# Main.net
KiCad netlist of a schematic drawn in Altium Designer
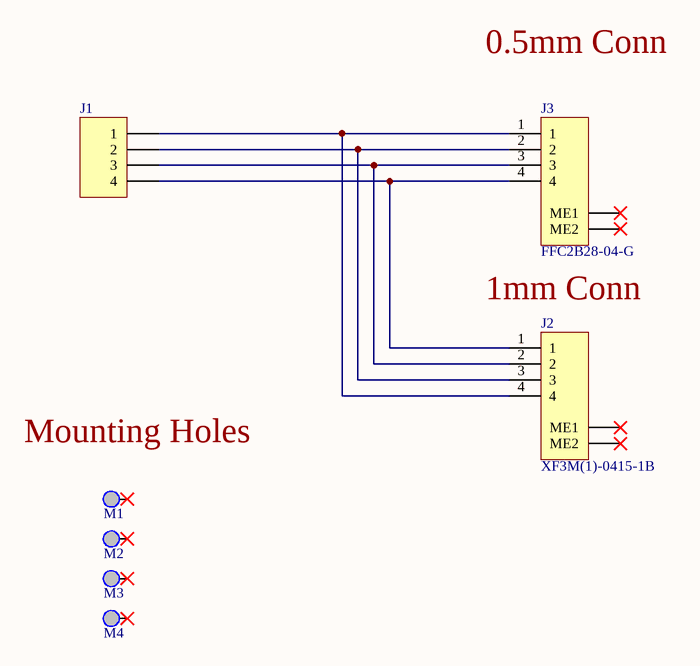
[diagram p0: Main.SchDoc]

(export (version "E")
  (design (tool "Eeschema 10.0.6"))
  (components
    (comp (ref "J1")
      (value "61300411121")
      (footprint "HDR-V-1X4")
      (description "Header, 4-Pin, 0.1\"")
      (libsource (lib "intercreate") (part "HDR-V-1X4-M"))
    )
    (comp (ref "J2")
      (value "XF3M(1)-0415-1B")
      (footprint "CONN-FFC-H-4P-1MM")
      (description "FFC & FPC Connectors RotaryBackLock 1.0mm Dual Contact 4pin")
      (libsource (lib "intercreate") (part "CONN-FFC-H-4P-1MM"))
    )
    (comp (ref "J3")
      (value "FFC2B28-04-G")
      (footprint "CONN-FFC-H-4P-0.5MM")
      (description "4W, 0.5MM Ffc Con, R/a, Dual Cont")
      (libsource (lib "intercreate") (part "CONN-FFC-H-4P-0.5MM"))
    )
    (comp (ref "M1")
      (value "MTG_HOLE")
      (footprint "MH_P_2.5MM")
      (description "MTG HOLE PLATED VARIOUS SIZES")
      (libsource (lib "intercreate") (part "MTG_HOLE"))
    )
    (comp (ref "M2")
      (value "MTG_HOLE")
      (footprint "MH_P_2.5MM")
      (description "MTG HOLE PLATED VARIOUS SIZES")
      (libsource (lib "intercreate") (part "MTG_HOLE"))
    )
    (comp (ref "M3")
      (value "MTG_HOLE")
      (footprint "MH_P_2.5MM")
      (description "MTG HOLE PLATED VARIOUS SIZES")
      (libsource (lib "intercreate") (part "MTG_HOLE"))
    )
    (comp (ref "M4")
      (value "MTG_HOLE")
      (footprint "MH_P_2.5MM")
      (description "MTG HOLE PLATED VARIOUS SIZES")
      (libsource (lib "intercreate") (part "MTG_HOLE"))
    )
  )
  (nets
    (net (code "1") (name "Net-(J1-Pad1)") (class "Default")
      (node (ref "J1") (pin "1") (pinfunction "1_1") (pintype "passive"))
      (node (ref "J2") (pin "4") (pinfunction "4_4") (pintype "passive"))
      (node (ref "J3") (pin "1") (pinfunction "1_1") (pintype "passive"))
    )
    (net (code "2") (name "Net-(J1-Pad2)") (class "Default")
      (node (ref "J1") (pin "2") (pinfunction "2_2") (pintype "passive"))
      (node (ref "J2") (pin "3") (pinfunction "3_3") (pintype "passive"))
      (node (ref "J3") (pin "2") (pinfunction "2_2") (pintype "passive"))
    )
    (net (code "3") (name "Net-(J1-Pad3)") (class "Default")
      (node (ref "J1") (pin "3") (pinfunction "3_3") (pintype "passive"))
      (node (ref "J2") (pin "2") (pinfunction "2_2") (pintype "passive"))
      (node (ref "J3") (pin "3") (pinfunction "3_3") (pintype "passive"))
    )
    (net (code "4") (name "Net-(J1-Pad4)") (class "Default")
      (node (ref "J1") (pin "4") (pinfunction "4_4") (pintype "passive"))
      (node (ref "J2") (pin "1") (pinfunction "1_1") (pintype "passive"))
      (node (ref "J3") (pin "4") (pinfunction "4_4") (pintype "passive"))
    )
    (net (code "5") (name "unconnected-(J2-PadME1)") (class "Default")
      (node (ref "J2") (pin "ME1") (pinfunction "ME1_ME1") (pintype "passive+no_connect"))
    )
    (net (code "6") (name "unconnected-(J2-PadME2)") (class "Default")
      (node (ref "J2") (pin "ME2") (pinfunction "ME2_ME2") (pintype "passive+no_connect"))
    )
    (net (code "7") (name "unconnected-(J3-PadME1)") (class "Default")
      (node (ref "J3") (pin "ME1") (pinfunction "ME1_ME1") (pintype "passive+no_connect"))
    )
    (net (code "8") (name "unconnected-(J3-PadME2)") (class "Default")
      (node (ref "J3") (pin "ME2") (pinfunction "ME2_ME2") (pintype "passive+no_connect"))
    )
    (net (code "9") (name "unconnected-(M1-Pad1)") (class "Default")
      (node (ref "M1") (pin "1") (pinfunction "1_1") (pintype "passive+no_connect"))
    )
    (net (code "10") (name "unconnected-(M2-Pad1)") (class "Default")
      (node (ref "M2") (pin "1") (pinfunction "1_1") (pintype "passive+no_connect"))
    )
    (net (code "11") (name "unconnected-(M3-Pad1)") (class "Default")
      (node (ref "M3") (pin "1") (pinfunction "1_1") (pintype "passive+no_connect"))
    )
    (net (code "12") (name "unconnected-(M4-Pad1)") (class "Default")
      (node (ref "M4") (pin "1") (pinfunction "1_1") (pintype "passive+no_connect"))
    )
  )
)
